# SSM_RGB.net
KiCad netlist of a schematic drawn in EAGLE
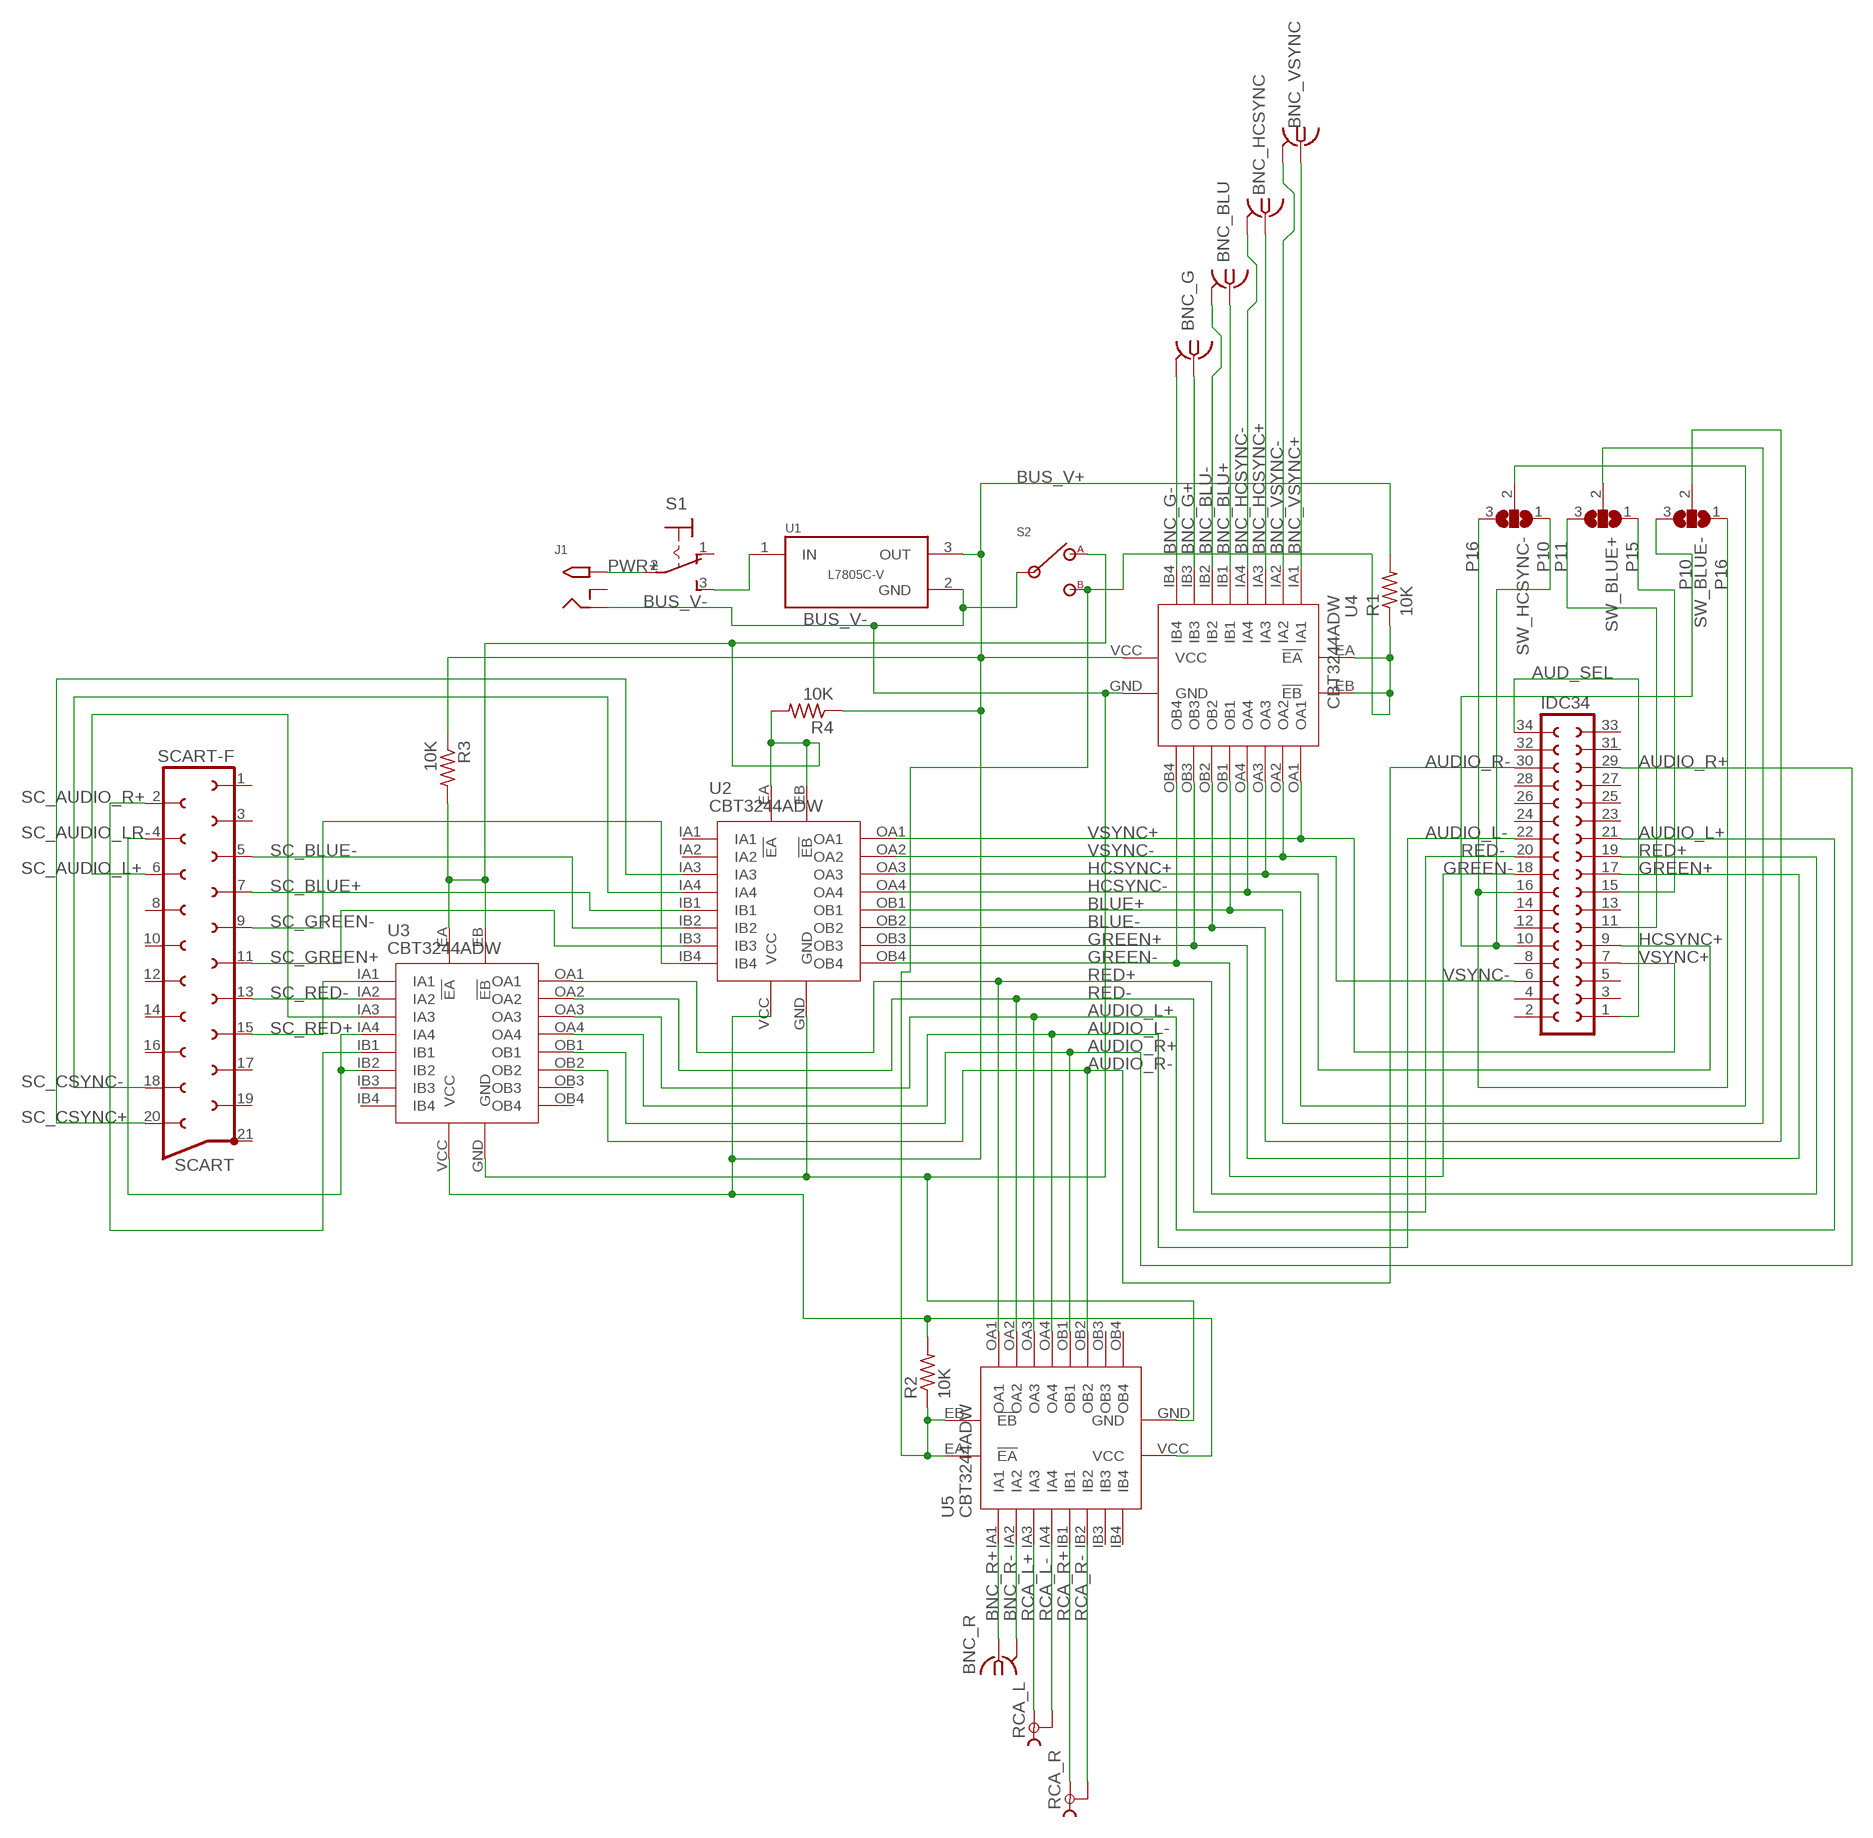
[diagram p0: schematic, sheet 1]

(export (version "E")
  (design (tool "Eeschema 10.0.6"))
  (components
    (comp (ref "BNC_BLU")
      (value "142142")
      (footprint "eagle-import:142142")
      (fields (field (name "MF") "Amphenol Connex"))
      (libsource (lib "eagle-import") (part "142142"))
    )
    (comp (ref "BNC_G")
      (value "142142")
      (footprint "eagle-import:142142")
      (fields (field (name "MF") "Amphenol Connex"))
      (libsource (lib "eagle-import") (part "142142"))
    )
    (comp (ref "BNC_HCSYNC")
      (value "142142")
      (footprint "eagle-import:142142")
      (fields (field (name "MF") "Amphenol Connex"))
      (libsource (lib "eagle-import") (part "142142"))
    )
    (comp (ref "BNC_R")
      (value "142142")
      (footprint "eagle-import:142142")
      (fields (field (name "MF") "Amphenol Connex"))
      (libsource (lib "eagle-import") (part "142142"))
    )
    (comp (ref "BNC_VSYNC")
      (value "142142")
      (footprint "eagle-import:142142")
      (fields (field (name "MF") "Amphenol Connex"))
      (libsource (lib "eagle-import") (part "142142"))
    )
    (comp (ref "IDC34")
      (value "SOCKET-34RA")
      (footprint "eagle-import:S34RA")
      (libsource (lib "eagle-import") (part "SOCKET-34RA"))
    )
    (comp (ref "J1")
      (value "2.1MMJACKTHM")
      (footprint "eagle-import:PJ-102A")
      (libsource (lib "eagle-import") (part "2.1MMJACKTHM"))
    )
    (comp (ref "R1")
      (value "10K")
      (footprint "eagle-import:0207_10")
      (libsource (lib "eagle-import") (part "R-US_0207/10"))
    )
    (comp (ref "R2")
      (value "10K")
      (footprint "eagle-import:0207_10")
      (libsource (lib "eagle-import") (part "R-US_0207/10"))
    )
    (comp (ref "R3")
      (value "10K")
      (footprint "eagle-import:0207_10")
      (libsource (lib "eagle-import") (part "R-US_0207/10"))
    )
    (comp (ref "R4")
      (value "10K")
      (footprint "eagle-import:0207_10")
      (libsource (lib "eagle-import") (part "R-US_0207/10"))
    )
    (comp (ref "RCA_L")
      (value "TOBU3")
      (footprint "eagle-import:TOBU3")
      (fields (field (name "MF") "FARNELL") (field (name "MPN") "TOBU 3"))
      (libsource (lib "eagle-import") (part "TOBU3"))
    )
    (comp (ref "RCA_R")
      (value "TOBU3")
      (footprint "eagle-import:TOBU3")
      (fields (field (name "MF") "FARNELL") (field (name "MPN") "TOBU 3"))
      (libsource (lib "eagle-import") (part "TOBU3"))
    )
    (comp (ref "S1")
      (value "320-916")
      (footprint "eagle-import:320-916")
      (libsource (lib "eagle-import") (part "320-916"))
    )
    (comp (ref "S2")
      (value "STS121PC04")
      (footprint "eagle-import:STS121PC04")
      (libsource (lib "eagle-import") (part "STS121PC04"))
    )
    (comp (ref "SCART")
      (value "SCART-F")
      (footprint "eagle-import:SCART-F")
      (libsource (lib "eagle-import") (part "SCART-F"))
    )
    (comp (ref "SW_BLUE+")
      (value "SJ2W")
      (footprint "eagle-import:SJ_2")
      (libsource (lib "eagle-import") (part "SJ2W"))
    )
    (comp (ref "SW_BLUE-")
      (value "SJ2W")
      (footprint "eagle-import:SJ_2")
      (libsource (lib "eagle-import") (part "SJ2W"))
    )
    (comp (ref "SW_HCSYNC-")
      (value "SJ2W")
      (footprint "eagle-import:SJ_2")
      (libsource (lib "eagle-import") (part "SJ2W"))
    )
    (comp (ref "U1")
      (value "L7805C-V")
      (footprint "eagle-import:TO254P460X1020X1945-3P")
      (fields
        (field (name "DIGI-KEY_PART_NUMBER") "497-1443-5-ND")
        (field (name "MF") "STMicroelectronics")
        (field (name "MP") "L7805CV")
      )
      (libsource (lib "eagle-import") (part "L7805C-V"))
    )
    (comp (ref "U2")
      (value "CBT3244ADW")
      (footprint "eagle-import:SOIC-20")
      (libsource (lib "eagle-import") (part "CBT3244ADW"))
    )
    (comp (ref "U3")
      (value "CBT3244ADW")
      (footprint "eagle-import:SOIC-20")
      (libsource (lib "eagle-import") (part "CBT3244ADW"))
    )
    (comp (ref "U4")
      (value "CBT3244ADW")
      (footprint "eagle-import:SOIC-20")
      (libsource (lib "eagle-import") (part "CBT3244ADW"))
    )
    (comp (ref "U5")
      (value "CBT3244ADW")
      (footprint "eagle-import:SOIC-20")
      (libsource (lib "eagle-import") (part "CBT3244ADW"))
    )
  )
  (nets
    (net (code "1") (name "/AUDIO_L+") (class "Default")
      (node (ref "IDC34") (pin "21") (pinfunction "21_21") (pintype "passive"))
      (node (ref "U3") (pin "OA3") (pinfunction "OA3_OA3") (pintype "output"))
      (node (ref "U5") (pin "OA3") (pinfunction "OA3_OA3") (pintype "output"))
    )
    (net (code "2") (name "/AUDIO_L-") (class "Default")
      (node (ref "IDC34") (pin "22") (pinfunction "22_22") (pintype "passive"))
      (node (ref "U3") (pin "OA4") (pinfunction "OA4_OA4") (pintype "output"))
      (node (ref "U5") (pin "OA4") (pinfunction "OA4_OA4") (pintype "output"))
    )
    (net (code "3") (name "/AUDIO_R+") (class "Default")
      (node (ref "IDC34") (pin "29") (pinfunction "29_29") (pintype "passive"))
      (node (ref "U3") (pin "OB1") (pinfunction "OB1_OB1") (pintype "output"))
      (node (ref "U5") (pin "OB1") (pinfunction "OB1_OB1") (pintype "output"))
    )
    (net (code "4") (name "/AUDIO_R-") (class "Default")
      (node (ref "IDC34") (pin "30") (pinfunction "30_30") (pintype "passive"))
      (node (ref "U3") (pin "OB2") (pinfunction "OB2_OB2") (pintype "output"))
      (node (ref "U5") (pin "OB2") (pinfunction "OB2_OB2") (pintype "output"))
    )
    (net (code "5") (name "/AUD_SEL") (class "Default")
      (node (ref "IDC34") (pin "1") (pinfunction "1_1") (pintype "passive"))
      (node (ref "IDC34") (pin "34") (pinfunction "34_34") (pintype "passive"))
    )
    (net (code "6") (name "/BLUE+") (class "Default")
      (node (ref "SW_BLUE+") (pin "2") (pinfunction "2_2") (pintype "passive"))
      (node (ref "U2") (pin "OB1") (pinfunction "OB1_OB1") (pintype "output"))
      (node (ref "U4") (pin "OB1") (pinfunction "OB1_OB1") (pintype "output"))
    )
    (net (code "7") (name "/BLUE-") (class "Default")
      (node (ref "SW_BLUE-") (pin "2") (pinfunction "2_2") (pintype "passive"))
      (node (ref "U2") (pin "OB2") (pinfunction "OB2_OB2") (pintype "output"))
      (node (ref "U4") (pin "OB2") (pinfunction "OB2_OB2") (pintype "output"))
    )
    (net (code "8") (name "/BNC_BLU+") (class "Default")
      (node (ref "BNC_BLU") (pin "1") (pinfunction "1_1") (pintype "passive"))
      (node (ref "U4") (pin "IB1") (pinfunction "IB1_IB1") (pintype "input"))
    )
    (net (code "9") (name "/BNC_BLU-") (class "Default")
      (node (ref "BNC_BLU") (pin "2") (pinfunction "2_2") (pintype "passive"))
      (node (ref "BNC_BLU") (pin "3") (pinfunction "2_3") (pintype "passive"))
      (node (ref "BNC_BLU") (pin "4") (pinfunction "2_4") (pintype "passive"))
      (node (ref "BNC_BLU") (pin "5") (pinfunction "2_5") (pintype "passive"))
      (node (ref "U4") (pin "IB2") (pinfunction "IB2_IB2") (pintype "input"))
    )
    (net (code "10") (name "/BNC_G+") (class "Default")
      (node (ref "BNC_G") (pin "1") (pinfunction "1_1") (pintype "passive"))
      (node (ref "U4") (pin "IB3") (pinfunction "IB3_IB3") (pintype "input"))
    )
    (net (code "11") (name "/BNC_G-") (class "Default")
      (node (ref "BNC_G") (pin "2") (pinfunction "2_2") (pintype "passive"))
      (node (ref "BNC_G") (pin "3") (pinfunction "2_3") (pintype "passive"))
      (node (ref "BNC_G") (pin "4") (pinfunction "2_4") (pintype "passive"))
      (node (ref "BNC_G") (pin "5") (pinfunction "2_5") (pintype "passive"))
      (node (ref "U4") (pin "IB4") (pinfunction "IB4_IB4") (pintype "input"))
    )
    (net (code "12") (name "/BNC_HCSYNC+") (class "Default")
      (node (ref "BNC_HCSYNC") (pin "1") (pinfunction "1_1") (pintype "passive"))
      (node (ref "U4") (pin "IA3") (pinfunction "IA3_IA3") (pintype "input"))
    )
    (net (code "13") (name "/BNC_HCSYNC-") (class "Default")
      (node (ref "BNC_HCSYNC") (pin "2") (pinfunction "2_2") (pintype "passive"))
      (node (ref "BNC_HCSYNC") (pin "3") (pinfunction "2_3") (pintype "passive"))
      (node (ref "BNC_HCSYNC") (pin "4") (pinfunction "2_4") (pintype "passive"))
      (node (ref "BNC_HCSYNC") (pin "5") (pinfunction "2_5") (pintype "passive"))
      (node (ref "U4") (pin "IA4") (pinfunction "IA4_IA4") (pintype "input"))
    )
    (net (code "14") (name "/BNC_R+") (class "Default")
      (node (ref "BNC_R") (pin "1") (pinfunction "1_1") (pintype "passive"))
      (node (ref "U5") (pin "IA1") (pinfunction "IA1_IA1") (pintype "input"))
    )
    (net (code "15") (name "/BNC_R-") (class "Default")
      (node (ref "BNC_R") (pin "2") (pinfunction "2_2") (pintype "passive"))
      (node (ref "BNC_R") (pin "3") (pinfunction "2_3") (pintype "passive"))
      (node (ref "BNC_R") (pin "4") (pinfunction "2_4") (pintype "passive"))
      (node (ref "BNC_R") (pin "5") (pinfunction "2_5") (pintype "passive"))
      (node (ref "U5") (pin "IA2") (pinfunction "IA2_IA2") (pintype "input"))
    )
    (net (code "16") (name "/BNC_VSYNC+") (class "Default")
      (node (ref "BNC_VSYNC") (pin "1") (pinfunction "1_1") (pintype "passive"))
      (node (ref "U4") (pin "IA1") (pinfunction "IA1_IA1") (pintype "input"))
    )
    (net (code "17") (name "/BNC_VSYNC-") (class "Default")
      (node (ref "BNC_VSYNC") (pin "2") (pinfunction "2_2") (pintype "passive"))
      (node (ref "BNC_VSYNC") (pin "3") (pinfunction "2_3") (pintype "passive"))
      (node (ref "BNC_VSYNC") (pin "4") (pinfunction "2_4") (pintype "passive"))
      (node (ref "BNC_VSYNC") (pin "5") (pinfunction "2_5") (pintype "passive"))
      (node (ref "U4") (pin "IA2") (pinfunction "IA2_IA2") (pintype "input"))
    )
    (net (code "18") (name "/BUS_V+") (class "Default")
      (node (ref "R1") (pin "2") (pinfunction "2_2") (pintype "passive"))
      (node (ref "R2") (pin "2") (pinfunction "2_2") (pintype "passive"))
      (node (ref "R3") (pin "1") (pinfunction "1_1") (pintype "passive"))
      (node (ref "R4") (pin "1") (pinfunction "1_1") (pintype "passive"))
      (node (ref "U1") (pin "3") (pinfunction "OUT_3") (pintype "output"))
      (node (ref "U2") (pin "VCC") (pinfunction "VCC_VCC") (pintype "power_in"))
      (node (ref "U3") (pin "VCC") (pinfunction "VCC_VCC") (pintype "power_in"))
      (node (ref "U4") (pin "VCC") (pinfunction "VCC_VCC") (pintype "power_in"))
      (node (ref "U5") (pin "VCC") (pinfunction "VCC_VCC") (pintype "power_in"))
    )
    (net (code "19") (name "/BUS_V-") (class "Default")
      (node (ref "J1") (pin "RING") (pinfunction "RING_RING") (pintype "bidirectional"))
      (node (ref "S2") (pin "2") (pinfunction "2_2") (pintype "bidirectional"))
      (node (ref "U1") (pin "2") (pinfunction "GND_2") (pintype "power_in"))
      (node (ref "U2") (pin "GND") (pinfunction "GND_GND") (pintype "power_in"))
      (node (ref "U3") (pin "GND") (pinfunction "GND_GND") (pintype "power_in"))
      (node (ref "U4") (pin "GND") (pinfunction "GND_GND") (pintype "power_in"))
      (node (ref "U5") (pin "GND") (pinfunction "GND_GND") (pintype "power_in"))
    )
    (net (code "20") (name "/GREEN+") (class "Default")
      (node (ref "IDC34") (pin "17") (pinfunction "17_17") (pintype "passive"))
      (node (ref "U2") (pin "OB3") (pinfunction "OB3_OB3") (pintype "output"))
      (node (ref "U4") (pin "OB3") (pinfunction "OB3_OB3") (pintype "output"))
    )
    (net (code "21") (name "/GREEN-") (class "Default")
      (node (ref "IDC34") (pin "18") (pinfunction "18_18") (pintype "passive"))
      (node (ref "U2") (pin "OB4") (pinfunction "OB4_OB4") (pintype "output"))
      (node (ref "U4") (pin "OB4") (pinfunction "OB4_OB4") (pintype "output"))
    )
    (net (code "22") (name "/HCSYNC+") (class "Default")
      (node (ref "IDC34") (pin "9") (pinfunction "9_9") (pintype "passive"))
      (node (ref "U2") (pin "OA3") (pinfunction "OA3_OA3") (pintype "output"))
      (node (ref "U4") (pin "OA3") (pinfunction "OA3_OA3") (pintype "output"))
    )
    (net (code "23") (name "/HCSYNC-") (class "Default")
      (node (ref "SW_HCSYNC-") (pin "2") (pinfunction "2_2") (pintype "passive"))
      (node (ref "U2") (pin "OA4") (pinfunction "OA4_OA4") (pintype "output"))
      (node (ref "U4") (pin "OA4") (pinfunction "OA4_OA4") (pintype "output"))
    )
    (net (code "24") (name "/P10") (class "Default")
      (node (ref "IDC34") (pin "10") (pinfunction "10_10") (pintype "passive"))
      (node (ref "SW_BLUE-") (pin "3") (pinfunction "3_3") (pintype "passive"))
      (node (ref "SW_HCSYNC-") (pin "1") (pinfunction "1_1") (pintype "passive"))
    )
    (net (code "25") (name "/P11") (class "Default")
      (node (ref "IDC34") (pin "11") (pinfunction "11_11") (pintype "passive"))
      (node (ref "SW_BLUE+") (pin "3") (pinfunction "3_3") (pintype "passive"))
    )
    (net (code "26") (name "/P15") (class "Default")
      (node (ref "IDC34") (pin "15") (pinfunction "15_15") (pintype "passive"))
      (node (ref "SW_BLUE+") (pin "1") (pinfunction "1_1") (pintype "passive"))
    )
    (net (code "27") (name "/P16") (class "Default")
      (node (ref "IDC34") (pin "16") (pinfunction "16_16") (pintype "passive"))
      (node (ref "SW_BLUE-") (pin "1") (pinfunction "1_1") (pintype "passive"))
      (node (ref "SW_HCSYNC-") (pin "3") (pinfunction "3_3") (pintype "passive"))
    )
    (net (code "28") (name "/PWR+") (class "Default")
      (node (ref "J1") (pin "TIP") (pinfunction "TIP_TIP") (pintype "bidirectional"))
      (node (ref "S1") (pin "2") (pinfunction "P_2") (pintype "passive"))
    )
    (net (code "29") (name "/RCA_L+") (class "Default")
      (node (ref "RCA_L") (pin "1") (pinfunction "1_1") (pintype "passive"))
      (node (ref "U5") (pin "IA3") (pinfunction "IA3_IA3") (pintype "input"))
    )
    (net (code "30") (name "/RCA_L-") (class "Default")
      (node (ref "RCA_L") (pin "2") (pinfunction "2_2") (pintype "passive"))
      (node (ref "RCA_L") (pin "2@1") (pinfunction "2_2@1") (pintype "passive"))
      (node (ref "RCA_L") (pin "2@2") (pinfunction "2_2@2") (pintype "passive"))
      (node (ref "U5") (pin "IA4") (pinfunction "IA4_IA4") (pintype "input"))
    )
    (net (code "31") (name "/RCA_R+") (class "Default")
      (node (ref "RCA_R") (pin "1") (pinfunction "1_1") (pintype "passive"))
      (node (ref "U5") (pin "IB1") (pinfunction "IB1_IB1") (pintype "input"))
    )
    (net (code "32") (name "/RCA_R-") (class "Default")
      (node (ref "RCA_R") (pin "2") (pinfunction "2_2") (pintype "passive"))
      (node (ref "RCA_R") (pin "2@1") (pinfunction "2_2@1") (pintype "passive"))
      (node (ref "RCA_R") (pin "2@2") (pinfunction "2_2@2") (pintype "passive"))
      (node (ref "U5") (pin "IB2") (pinfunction "IB2_IB2") (pintype "input"))
    )
    (net (code "33") (name "/RED+") (class "Default")
      (node (ref "IDC34") (pin "19") (pinfunction "19_19") (pintype "passive"))
      (node (ref "U3") (pin "OA1") (pinfunction "OA1_OA1") (pintype "output"))
      (node (ref "U5") (pin "OA1") (pinfunction "OA1_OA1") (pintype "output"))
    )
    (net (code "34") (name "/RED-") (class "Default")
      (node (ref "IDC34") (pin "20") (pinfunction "20_20") (pintype "passive"))
      (node (ref "U3") (pin "OA2") (pinfunction "OA2_OA2") (pintype "output"))
      (node (ref "U5") (pin "OA2") (pinfunction "OA2_OA2") (pintype "output"))
    )
    (net (code "35") (name "/SC_AUDIO_L+") (class "Default")
      (node (ref "SCART") (pin "6") (pinfunction "6_6") (pintype "passive"))
      (node (ref "U3") (pin "IA3") (pinfunction "IA3_IA3") (pintype "input"))
    )
    (net (code "36") (name "/SC_AUDIO_LR-") (class "Default")
      (node (ref "SCART") (pin "4") (pinfunction "4_4") (pintype "passive"))
      (node (ref "U3") (pin "IA4") (pinfunction "IA4_IA4") (pintype "input"))
      (node (ref "U3") (pin "IB2") (pinfunction "IB2_IB2") (pintype "input"))
    )
    (net (code "37") (name "/SC_AUDIO_R+") (class "Default")
      (node (ref "SCART") (pin "2") (pinfunction "2_2") (pintype "passive"))
      (node (ref "U3") (pin "IB1") (pinfunction "IB1_IB1") (pintype "input"))
    )
    (net (code "38") (name "/SC_BLUE+") (class "Default")
      (node (ref "SCART") (pin "7") (pinfunction "7_7") (pintype "passive"))
      (node (ref "U2") (pin "IB1") (pinfunction "IB1_IB1") (pintype "input"))
    )
    (net (code "39") (name "/SC_BLUE-") (class "Default")
      (node (ref "SCART") (pin "5") (pinfunction "5_5") (pintype "passive"))
      (node (ref "U2") (pin "IB2") (pinfunction "IB2_IB2") (pintype "input"))
    )
    (net (code "40") (name "/SC_CSYNC+") (class "Default")
      (node (ref "SCART") (pin "20") (pinfunction "20_20") (pintype "passive"))
      (node (ref "U2") (pin "IA3") (pinfunction "IA3_IA3") (pintype "input"))
    )
    (net (code "41") (name "/SC_CSYNC-") (class "Default")
      (node (ref "SCART") (pin "18") (pinfunction "18_18") (pintype "passive"))
      (node (ref "U2") (pin "IA4") (pinfunction "IA4_IA4") (pintype "input"))
    )
    (net (code "42") (name "/SC_GREEN+") (class "Default")
      (node (ref "SCART") (pin "11") (pinfunction "11_11") (pintype "passive"))
      (node (ref "U2") (pin "IB3") (pinfunction "IB3_IB3") (pintype "input"))
    )
    (net (code "43") (name "/SC_GREEN-") (class "Default")
      (node (ref "SCART") (pin "9") (pinfunction "9_9") (pintype "passive"))
      (node (ref "U2") (pin "IB4") (pinfunction "IB4_IB4") (pintype "input"))
    )
    (net (code "44") (name "/SC_RED+") (class "Default")
      (node (ref "SCART") (pin "15") (pinfunction "15_15") (pintype "passive"))
      (node (ref "U3") (pin "IA1") (pinfunction "IA1_IA1") (pintype "input"))
    )
    (net (code "45") (name "/SC_RED-") (class "Default")
      (node (ref "SCART") (pin "13") (pinfunction "13_13") (pintype "passive"))
      (node (ref "U3") (pin "IA2") (pinfunction "IA2_IA2") (pintype "input"))
    )
    (net (code "46") (name "/VSYNC+") (class "Default")
      (node (ref "IDC34") (pin "7") (pinfunction "7_7") (pintype "passive"))
      (node (ref "U2") (pin "OA1") (pinfunction "OA1_OA1") (pintype "output"))
      (node (ref "U4") (pin "OA1") (pinfunction "OA1_OA1") (pintype "output"))
    )
    (net (code "47") (name "/VSYNC-") (class "Default")
      (node (ref "IDC34") (pin "6") (pinfunction "6_6") (pintype "passive"))
      (node (ref "U2") (pin "OA2") (pinfunction "OA2_OA2") (pintype "output"))
      (node (ref "U4") (pin "OA2") (pinfunction "OA2_OA2") (pintype "output"))
    )
    (net (code "48") (name "Net-(S1-S)") (class "Default")
      (node (ref "S1") (pin "3") (pinfunction "S_3") (pintype "passive"))
      (node (ref "U1") (pin "1") (pinfunction "IN_1") (pintype "input"))
    )
    (net (code "49") (name "Net-(U2-~{EA})") (class "Default")
      (node (ref "R3") (pin "2") (pinfunction "2_2") (pintype "passive"))
      (node (ref "R4") (pin "2") (pinfunction "2_2") (pintype "passive"))
      (node (ref "S2") (pin "1") (pinfunction "1_1") (pintype "bidirectional"))
      (node (ref "U2") (pin "EA") (pinfunction "~{EA}_EA") (pintype "power_in"))
      (node (ref "U2") (pin "EB") (pinfunction "~{EB}_EB") (pintype "power_in"))
      (node (ref "U3") (pin "EA") (pinfunction "~{EA}_EA") (pintype "power_in"))
      (node (ref "U3") (pin "EB") (pinfunction "~{EB}_EB") (pintype "power_in"))
    )
    (net (code "50") (name "Net-(U4-~{EA})") (class "Default")
      (node (ref "R1") (pin "1") (pinfunction "1_1") (pintype "passive"))
      (node (ref "R2") (pin "1") (pinfunction "1_1") (pintype "passive"))
      (node (ref "S2") (pin "3") (pinfunction "3_3") (pintype "bidirectional"))
      (node (ref "U4") (pin "EA") (pinfunction "~{EA}_EA") (pintype "power_in"))
      (node (ref "U4") (pin "EB") (pinfunction "~{EB}_EB") (pintype "power_in"))
      (node (ref "U5") (pin "EA") (pinfunction "~{EA}_EA") (pintype "power_in"))
      (node (ref "U5") (pin "EB") (pinfunction "~{EB}_EB") (pintype "power_in"))
    )
    (net (code "51") (name "unconnected-(IDC34-Pad2)") (class "Default")
      (node (ref "IDC34") (pin "2") (pinfunction "2_2") (pintype "passive"))
    )
    (net (code "52") (name "unconnected-(IDC34-Pad3)") (class "Default")
      (node (ref "IDC34") (pin "3") (pinfunction "3_3") (pintype "passive"))
    )
    (net (code "53") (name "unconnected-(IDC34-Pad4)") (class "Default")
      (node (ref "IDC34") (pin "4") (pinfunction "4_4") (pintype "passive"))
    )
    (net (code "54") (name "unconnected-(IDC34-Pad5)") (class "Default")
      (node (ref "IDC34") (pin "5") (pinfunction "5_5") (pintype "passive"))
    )
    (net (code "55") (name "unconnected-(IDC34-Pad8)") (class "Default")
      (node (ref "IDC34") (pin "8") (pinfunction "8_8") (pintype "passive"))
    )
    (net (code "56") (name "unconnected-(IDC34-Pad12)") (class "Default")
      (node (ref "IDC34") (pin "12") (pinfunction "12_12") (pintype "passive"))
    )
    (net (code "57") (name "unconnected-(IDC34-Pad13)") (class "Default")
      (node (ref "IDC34") (pin "13") (pinfunction "13_13") (pintype "passive"))
    )
    (net (code "58") (name "unconnected-(IDC34-Pad14)") (class "Default")
      (node (ref "IDC34") (pin "14") (pinfunction "14_14") (pintype "passive"))
    )
    (net (code "59") (name "unconnected-(IDC34-Pad23)") (class "Default")
      (node (ref "IDC34") (pin "23") (pinfunction "23_23") (pintype "passive"))
    )
    (net (code "60") (name "unconnected-(IDC34-Pad24)") (class "Default")
      (node (ref "IDC34") (pin "24") (pinfunction "24_24") (pintype "passive"))
    )
    (net (code "61") (name "unconnected-(IDC34-Pad25)") (class "Default")
      (node (ref "IDC34") (pin "25") (pinfunction "25_25") (pintype "passive"))
    )
    (net (code "62") (name "unconnected-(IDC34-Pad26)") (class "Default")
      (node (ref "IDC34") (pin "26") (pinfunction "26_26") (pintype "passive"))
    )
    (net (code "63") (name "unconnected-(IDC34-Pad27)") (class "Default")
      (node (ref "IDC34") (pin "27") (pinfunction "27_27") (pintype "passive"))
    )
    (net (code "64") (name "unconnected-(IDC34-Pad28)") (class "Default")
      (node (ref "IDC34") (pin "28") (pinfunction "28_28") (pintype "passive"))
    )
    (net (code "65") (name "unconnected-(IDC34-Pad31)") (class "Default")
      (node (ref "IDC34") (pin "31") (pinfunction "31_31") (pintype "passive"))
    )
    (net (code "66") (name "unconnected-(IDC34-Pad32)") (class "Default")
      (node (ref "IDC34") (pin "32") (pinfunction "32_32") (pintype "passive"))
    )
    (net (code "67") (name "unconnected-(IDC34-Pad33)") (class "Default")
      (node (ref "IDC34") (pin "33") (pinfunction "33_33") (pintype "passive"))
    )
    (net (code "68") (name "unconnected-(J1-PadRING_SW)") (class "Default")
      (node (ref "J1") (pin "RING_SW") (pinfunction "RING_SW_RING_SW") (pintype "bidirectional"))
    )
    (net (code "69") (name "unconnected-(S1-O-Pad1)") (class "Default")
      (node (ref "S1") (pin "1") (pinfunction "O_1") (pintype "passive"))
    )
    (net (code "70") (name "unconnected-(SCART-Pad1)") (class "Default")
      (node (ref "SCART") (pin "1") (pinfunction "1_1") (pintype "passive"))
    )
    (net (code "71") (name "unconnected-(SCART-Pad3)") (class "Default")
      (node (ref "SCART") (pin "3") (pinfunction "3_3") (pintype "passive"))
    )
    (net (code "72") (name "unconnected-(SCART-Pad8)") (class "Default")
      (node (ref "SCART") (pin "8") (pinfunction "8_8") (pintype "passive"))
    )
    (net (code "73") (name "unconnected-(SCART-Pad10)") (class "Default")
      (node (ref "SCART") (pin "10") (pinfunction "10_10") (pintype "passive"))
    )
    (net (code "74") (name "unconnected-(SCART-Pad12)") (class "Default")
      (node (ref "SCART") (pin "12") (pinfunction "12_12") (pintype "passive"))
    )
    (net (code "75") (name "unconnected-(SCART-Pad14)") (class "Default")
      (node (ref "SCART") (pin "14") (pinfunction "14_14") (pintype "passive"))
    )
    (net (code "76") (name "unconnected-(SCART-Pad16)") (class "Default")
      (node (ref "SCART") (pin "16") (pinfunction "16_16") (pintype "passive"))
    )
    (net (code "77") (name "unconnected-(SCART-Pad17)") (class "Default")
      (node (ref "SCART") (pin "17") (pinfunction "17_17") (pintype "passive"))
    )
    (net (code "78") (name "unconnected-(SCART-Pad19)") (class "Default")
      (node (ref "SCART") (pin "19") (pinfunction "19_19") (pintype "passive"))
    )
    (net (code "79") (name "unconnected-(SCART-Pad21)") (class "Default")
      (node (ref "SCART") (pin "21") (pinfunction "21_21") (pintype "passive"))
    )
    (net (code "80") (name "unconnected-(U2-PadIA1)") (class "Default")
      (node (ref "U2") (pin "IA1") (pinfunction "IA1_IA1") (pintype "input"))
    )
    (net (code "81") (name "unconnected-(U2-PadIA2)") (class "Default")
      (node (ref "U2") (pin "IA2") (pinfunction "IA2_IA2") (pintype "input"))
    )
    (net (code "82") (name "unconnected-(U3-PadIB3)") (class "Default")
      (node (ref "U3") (pin "IB3") (pinfunction "IB3_IB3") (pintype "input"))
    )
    (net (code "83") (name "unconnected-(U3-PadIB4)") (class "Default")
      (node (ref "U3") (pin "IB4") (pinfunction "IB4_IB4") (pintype "input"))
    )
    (net (code "84") (name "unconnected-(U3-PadOB3)") (class "Default")
      (node (ref "U3") (pin "OB3") (pinfunction "OB3_OB3") (pintype "output"))
    )
    (net (code "85") (name "unconnected-(U3-PadOB4)") (class "Default")
      (node (ref "U3") (pin "OB4") (pinfunction "OB4_OB4") (pintype "output"))
    )
    (net (code "86") (name "unconnected-(U5-PadIB3)") (class "Default")
      (node (ref "U5") (pin "IB3") (pinfunction "IB3_IB3") (pintype "input"))
    )
    (net (code "87") (name "unconnected-(U5-PadIB4)") (class "Default")
      (node (ref "U5") (pin "IB4") (pinfunction "IB4_IB4") (pintype "input"))
    )
    (net (code "88") (name "unconnected-(U5-PadOB3)") (class "Default")
      (node (ref "U5") (pin "OB3") (pinfunction "OB3_OB3") (pintype "output"))
    )
    (net (code "89") (name "unconnected-(U5-PadOB4)") (class "Default")
      (node (ref "U5") (pin "OB4") (pinfunction "OB4_OB4") (pintype "output"))
    )
  )
)
